# CPU.net
KiCad netlist of a schematic drawn in Altium Designer
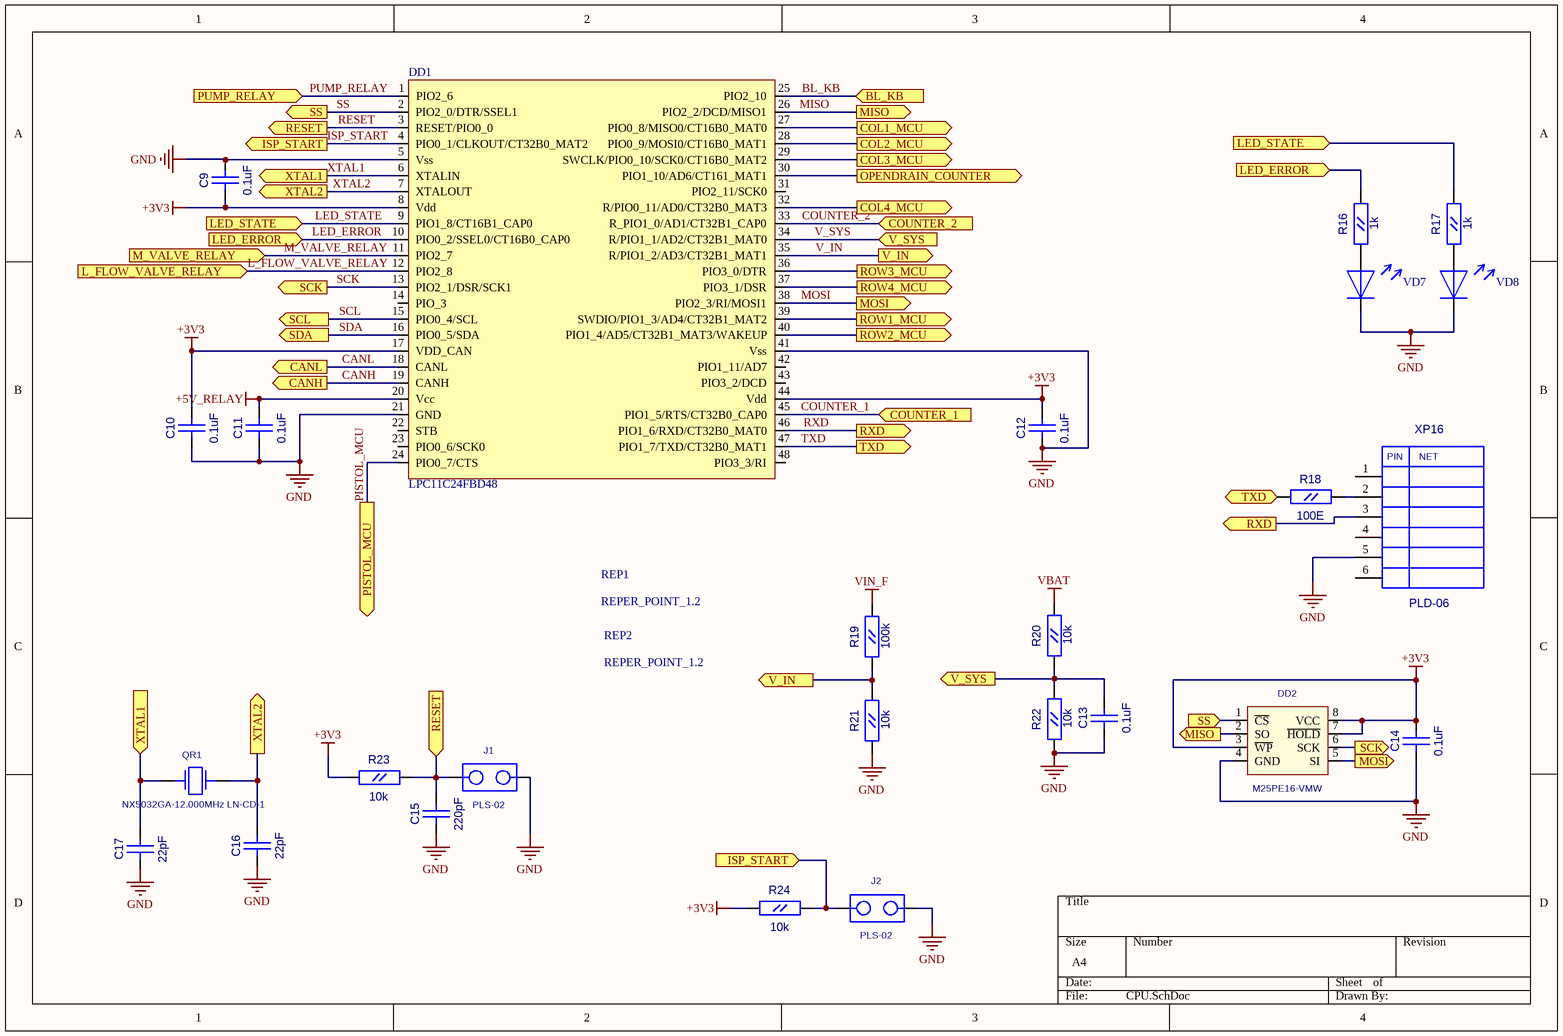
[diagram p0: CPU.SchDoc]

(export (version "E")
  (design (tool "Eeschema 10.0.6"))
  (components
    (comp (ref "C9")
      (value "0.1uF")
      (footprint "CC0603")
      (description "CC0603")
      (libsource (lib "gprs_modem_2") (part "CC0603"))
    )
    (comp (ref "C10")
      (value "0.1uF")
      (footprint "CC0603")
      (description "CC0603")
      (libsource (lib "gprs_modem_2") (part "CC0603"))
    )
    (comp (ref "C11")
      (value "0.1uF")
      (footprint "CC0603")
      (description "CC0603")
      (libsource (lib "gprs_modem_2") (part "CC0603"))
    )
    (comp (ref "C12")
      (value "0.1uF")
      (footprint "CC0603")
      (description "CC0603")
      (libsource (lib "gprs_modem_2") (part "CC0603"))
    )
    (comp (ref "C13")
      (value "0.1uF")
      (footprint "CC0603")
      (description "CC0603")
      (libsource (lib "gprs_modem_2") (part "CC0603"))
    )
    (comp (ref "C14")
      (value "0.1uF")
      (footprint "CC0603")
      (description "CC0603")
      (libsource (lib "gprs_modem_2") (part "CC0603"))
    )
    (comp (ref "C15")
      (value "220pF")
      (footprint "CC0603")
      (description "CC0603")
      (libsource (lib "gprs_modem_2") (part "CC0603"))
    )
    (comp (ref "C16")
      (value "22pF")
      (footprint "CC0603")
      (description "CC0603")
      (libsource (lib "gprs_modem_2") (part "CC0603"))
    )
    (comp (ref "C17")
      (value "22pF")
      (footprint "CC0603")
      (description "CC0603")
      (libsource (lib "gprs_modem_2") (part "CC0603"))
    )
    (comp (ref "DD1")
      (value "LPC11C24FBD48")
      (footprint "LQFP-48")
      (libsource (lib "gprs_modem_2") (part "LPC11C24FBD48"))
    )
    (comp (ref "DD2")
      (value "M25PE16-VMW")
      (footprint "EIAJ_SO8")
      (description "S25FL016A0LMFI01")
      (libsource (lib "gprs_modem_2") (part "S25FL016A0LMFI01"))
    )
    (comp (ref "J1") (value "PLS-02") (footprint "PLS-02") (libsource (lib "gprs_modem_2") (part "PLS-02")))
    (comp (ref "J2") (value "PLS-02") (footprint "PLS-02") (libsource (lib "gprs_modem_2") (part "PLS-02")))
    (comp (ref "QR1")
      (value "NX5032GA-12.000MHz LN-CD-1")
      (footprint "AC5032_2")
      (description "AC5032/2")
      (libsource (lib "gprs_modem_2") (part "AC5032_2"))
    )
    (comp (ref "R16")
      (value "1k")
      (footprint "RC0603")
      (description "RC0603")
      (libsource (lib "gprs_modem_2") (part "RC0603"))
    )
    (comp (ref "R17")
      (value "1k")
      (footprint "RC0603")
      (description "RC0603")
      (libsource (lib "gprs_modem_2") (part "RC0603"))
    )
    (comp (ref "R18")
      (value "100E")
      (footprint "RC0603")
      (description "RC0603")
      (libsource (lib "gprs_modem_2") (part "RC0603"))
    )
    (comp (ref "R19")
      (value "100k")
      (footprint "RC0603")
      (description "RC0603")
      (libsource (lib "gprs_modem_2") (part "RC0603"))
    )
    (comp (ref "R20")
      (value "10k")
      (footprint "RC0603")
      (description "RC0603")
      (libsource (lib "gprs_modem_2") (part "RC0603"))
    )
    (comp (ref "R21")
      (value "10k")
      (footprint "RC0603")
      (description "RC0603")
      (libsource (lib "gprs_modem_2") (part "RC0603"))
    )
    (comp (ref "R22")
      (value "10k")
      (footprint "RC0603")
      (description "RC0603")
      (libsource (lib "gprs_modem_2") (part "RC0603"))
    )
    (comp (ref "R23")
      (value "10k")
      (footprint "RC0603")
      (description "RC0603")
      (libsource (lib "gprs_modem_2") (part "RC0603"))
    )
    (comp (ref "R24")
      (value "10k")
      (footprint "RC0603")
      (description "RC0603")
      (libsource (lib "gprs_modem_2") (part "RC0603"))
    )
    (comp (ref "REP1")
      (value "REPER_POINT_1.2")
      (footprint "REPER1.2")
      (description "REPER1.2")
      (libsource (lib "gprs_modem_2") (part "REPER1.2"))
    )
    (comp (ref "REP2")
      (value "REPER_POINT_1.2")
      (footprint "REPER1.2")
      (description "REPER1.2")
      (libsource (lib "gprs_modem_2") (part "REPER1.2"))
    )
    (comp (ref "VD7")
      (value "LED_0805")
      (footprint "LED0805")
      (libsource (lib "gprs_modem_2") (part "LED_0805"))
    )
    (comp (ref "VD8")
      (value "LED_0805")
      (footprint "LED0805")
      (libsource (lib "gprs_modem_2") (part "LED_0805"))
    )
    (comp (ref "XP16")
      (value "PLD-06")
      (footprint "PIN6")
      (description "PLD06")
      (libsource (lib "gprs_modem_2") (part "PLD-06"))
    )
  )
  (nets
    (net (code "1") (name "+3V3") (class "Default")
      (node (ref "C10") (pin "2") (pinfunction "B_2") (pintype "passive"))
      (node (ref "C12") (pin "2") (pinfunction "B_2") (pintype "passive"))
      (node (ref "C14") (pin "2") (pinfunction "B_2") (pintype "passive"))
      (node (ref "C9") (pin "1") (pinfunction "A_1") (pintype "passive"))
      (node (ref "DD1") (pin "17") (pinfunction "VDD_CAN_17") (pintype "passive"))
      (node (ref "DD1") (pin "44") (pinfunction "Vdd_44") (pintype "passive"))
      (node (ref "DD1") (pin "8") (pinfunction "Vdd_8") (pintype "passive"))
      (node (ref "DD2") (pin "3") (pinfunction "~{WP}_3") (pintype "passive"))
      (node (ref "DD2") (pin "7") (pinfunction "~{HOLD}_7") (pintype "passive"))
      (node (ref "DD2") (pin "8") (pinfunction "VCC_8") (pintype "passive"))
      (node (ref "R23") (pin "1") (pinfunction "A_1") (pintype "passive"))
      (node (ref "R24") (pin "1") (pinfunction "A_1") (pintype "passive"))
    )
    (net (code "2") (name "+5V_RELAY") (class "Default")
      (node (ref "C11") (pin "2") (pinfunction "B_2") (pintype "passive"))
      (node (ref "DD1") (pin "20") (pinfunction "Vcc_20") (pintype "passive"))
    )
    (net (code "3") (name "/BL_KB") (class "Default")
      (node (ref "DD1") (pin "25") (pinfunction "PIO2_10_25") (pintype "passive"))
    )
    (net (code "4") (name "/CANH") (class "Default")
      (node (ref "DD1") (pin "19") (pinfunction "CANH_19") (pintype "passive"))
    )
    (net (code "5") (name "/CANL") (class "Default")
      (node (ref "DD1") (pin "18") (pinfunction "CANL_18") (pintype "passive"))
    )
    (net (code "6") (name "/COL1_MCU") (class "Default")
      (node (ref "DD1") (pin "27") (pinfunction "PIO0_8/MISO0/CT16B0_MAT0_27") (pintype "passive"))
    )
    (net (code "7") (name "/COL2_MCU") (class "Default")
      (node (ref "DD1") (pin "28") (pinfunction "PIO0_9/MOSI0/CT16B0_MAT1_28") (pintype "passive"))
    )
    (net (code "8") (name "/COL3_MCU") (class "Default")
      (node (ref "DD1") (pin "29") (pinfunction "SWCLK/PIO0_10/SCK0/CT16B0_MAT2_29") (pintype "passive"))
    )
    (net (code "9") (name "/COL4_MCU") (class "Default")
      (node (ref "DD1") (pin "32") (pinfunction "R/PIO0_11/AD0/CT32B0_MAT3_32") (pintype "passive"))
    )
    (net (code "10") (name "/COUNTER_1") (class "Default")
      (node (ref "DD1") (pin "45") (pinfunction "PIO1_5/RTS/CT32B0_CAP0_45") (pintype "passive"))
    )
    (net (code "11") (name "/COUNTER_2") (class "Default")
      (node (ref "DD1") (pin "33") (pinfunction "R_PIO1_0/AD1/CT32B1_CAP0_33") (pintype "passive"))
    )
    (net (code "12") (name "/ISP_START") (class "Default")
      (node (ref "DD1") (pin "4") (pinfunction "PIO0_1/CLKOUT/CT32B0_MAT2_4") (pintype "passive"))
      (node (ref "J2") (pin "1") (pintype "passive"))
      (node (ref "R24") (pin "2") (pinfunction "B_2") (pintype "passive"))
    )
    (net (code "13") (name "/LED_ERROR") (class "Default")
      (node (ref "DD1") (pin "10") (pinfunction "PIO0_2/SSEL0/CT16B0_CAP0_10") (pintype "passive"))
      (node (ref "R16") (pin "2") (pinfunction "B_2") (pintype "passive"))
    )
    (net (code "14") (name "/LED_STATE") (class "Default")
      (node (ref "DD1") (pin "9") (pinfunction "PIO1_8/CT16B1_CAP0_9") (pintype "passive"))
      (node (ref "R17") (pin "2") (pinfunction "B_2") (pintype "passive"))
    )
    (net (code "15") (name "/L_FLOW_VALVE_RELAY") (class "Default")
      (node (ref "DD1") (pin "12") (pinfunction "PIO2_8_12") (pintype "passive"))
    )
    (net (code "16") (name "/MISO") (class "Default")
      (node (ref "DD1") (pin "26") (pinfunction "PIO2_2/DCD/MISO1_26") (pintype "passive"))
      (node (ref "DD2") (pin "2") (pinfunction "SO_2") (pintype "passive"))
    )
    (net (code "17") (name "/MOSI") (class "Default")
      (node (ref "DD1") (pin "38") (pinfunction "PIO2_3/RI/MOSI1_38") (pintype "passive"))
      (node (ref "DD2") (pin "5") (pinfunction "SI_5") (pintype "passive"))
    )
    (net (code "18") (name "/M_VALVE_RELAY") (class "Default")
      (node (ref "DD1") (pin "11") (pinfunction "PIO2_7_11") (pintype "passive"))
    )
    (net (code "19") (name "/OPENDRAIN_COUNTER") (class "Default")
      (node (ref "DD1") (pin "30") (pinfunction "PIO1_10/AD6/CT161_MAT1_30") (pintype "passive"))
    )
    (net (code "20") (name "/PISTOL_MCU") (class "Default")
      (node (ref "DD1") (pin "24") (pinfunction "PIO0_7/CTS_24") (pintype "passive"))
    )
    (net (code "21") (name "/PUMP_RELAY") (class "Default")
      (node (ref "DD1") (pin "1") (pinfunction "PIO2_6_1") (pintype "passive"))
    )
    (net (code "22") (name "/RESET") (class "Default")
      (node (ref "C15") (pin "2") (pinfunction "B_2") (pintype "passive"))
      (node (ref "DD1") (pin "3") (pinfunction "RESET/PIO0_0_3") (pintype "passive"))
      (node (ref "J1") (pin "1") (pintype "passive"))
      (node (ref "R23") (pin "2") (pinfunction "B_2") (pintype "passive"))
    )
    (net (code "23") (name "/ROW1_MCU") (class "Default")
      (node (ref "DD1") (pin "39") (pinfunction "SWDIO/PIO1_3/AD4/CT32B1_MAT2_39") (pintype "passive"))
    )
    (net (code "24") (name "/ROW2_MCU") (class "Default")
      (node (ref "DD1") (pin "40") (pinfunction "PIO1_4/AD5/CT32B1_MAT3/WAKEUP_40") (pintype "passive"))
    )
    (net (code "25") (name "/ROW3_MCU") (class "Default")
      (node (ref "DD1") (pin "36") (pinfunction "PIO3_0/DTR_36") (pintype "passive"))
    )
    (net (code "26") (name "/ROW4_MCU") (class "Default")
      (node (ref "DD1") (pin "37") (pinfunction "PIO3_1/DSR_37") (pintype "passive"))
    )
    (net (code "27") (name "/RXD") (class "Default")
      (node (ref "DD1") (pin "46") (pinfunction "PIO1_6/RXD/CT32B0_MAT0_46") (pintype "passive"))
      (node (ref "XP16") (pin "3") (pinfunction "3_3") (pintype "passive"))
    )
    (net (code "28") (name "/SCK") (class "Default")
      (node (ref "DD1") (pin "13") (pinfunction "PIO2_1/DSR/SCK1_13") (pintype "passive"))
      (node (ref "DD2") (pin "6") (pinfunction "SCK_6") (pintype "passive"))
    )
    (net (code "29") (name "/SCL") (class "Default")
      (node (ref "DD1") (pin "15") (pinfunction "PIO0_4/SCL_15") (pintype "passive"))
    )
    (net (code "30") (name "/SDA") (class "Default")
      (node (ref "DD1") (pin "16") (pinfunction "PIO0_5/SDA_16") (pintype "passive"))
    )
    (net (code "31") (name "/SS") (class "Default")
      (node (ref "DD1") (pin "2") (pinfunction "PIO2_0/DTR/SSEL1_2") (pintype "passive"))
      (node (ref "DD2") (pin "1") (pinfunction "~{CS}_1") (pintype "passive"))
    )
    (net (code "32") (name "/TXD") (class "Default")
      (node (ref "DD1") (pin "47") (pinfunction "PIO1_7/TXD/CT32B0_MAT1_47") (pintype "passive"))
      (node (ref "R18") (pin "1") (pinfunction "A_1") (pintype "passive"))
    )
    (net (code "33") (name "/V_IN") (class "Default")
      (node (ref "DD1") (pin "35") (pinfunction "R/PIO1_2/AD3/CT32B1_MAT1_35") (pintype "passive"))
      (node (ref "R19") (pin "1") (pinfunction "A_1") (pintype "passive"))
      (node (ref "R21") (pin "2") (pinfunction "B_2") (pintype "passive"))
    )
    (net (code "34") (name "/V_SYS") (class "Default")
      (node (ref "C13") (pin "2") (pinfunction "B_2") (pintype "passive"))
      (node (ref "DD1") (pin "34") (pinfunction "R/PIO1_1/AD2/CT32B1_MAT0_34") (pintype "passive"))
      (node (ref "R20") (pin "1") (pinfunction "A_1") (pintype "passive"))
      (node (ref "R22") (pin "2") (pinfunction "B_2") (pintype "passive"))
    )
    (net (code "35") (name "/XTAL1") (class "Default")
      (node (ref "C17") (pin "2") (pinfunction "B_2") (pintype "passive"))
      (node (ref "DD1") (pin "6") (pinfunction "XTALIN_6") (pintype "passive"))
      (node (ref "QR1") (pin "1") (pintype "passive"))
    )
    (net (code "36") (name "/XTAL2") (class "Default")
      (node (ref "C16") (pin "2") (pinfunction "B_2") (pintype "passive"))
      (node (ref "DD1") (pin "7") (pinfunction "XTALOUT_7") (pintype "passive"))
      (node (ref "QR1") (pin "2") (pintype "passive"))
    )
    (net (code "37") (name "GND") (class "Default")
      (node (ref "C10") (pin "1") (pinfunction "A_1") (pintype "passive"))
      (node (ref "C11") (pin "1") (pinfunction "A_1") (pintype "passive"))
      (node (ref "C12") (pin "1") (pinfunction "A_1") (pintype "passive"))
      (node (ref "C13") (pin "1") (pinfunction "A_1") (pintype "passive"))
      (node (ref "C14") (pin "1") (pinfunction "A_1") (pintype "passive"))
      (node (ref "C15") (pin "1") (pinfunction "A_1") (pintype "passive"))
      (node (ref "C16") (pin "1") (pinfunction "A_1") (pintype "passive"))
      (node (ref "C17") (pin "1") (pinfunction "A_1") (pintype "passive"))
      (node (ref "C9") (pin "2") (pinfunction "B_2") (pintype "passive"))
      (node (ref "DD1") (pin "21") (pinfunction "GND_21") (pintype "passive"))
      (node (ref "DD1") (pin "41") (pinfunction "Vss_41") (pintype "passive"))
      (node (ref "DD1") (pin "5") (pinfunction "Vss_5") (pintype "passive"))
      (node (ref "DD2") (pin "4") (pinfunction "GND_4") (pintype "passive"))
      (node (ref "J1") (pin "2") (pintype "passive"))
      (node (ref "J2") (pin "2") (pintype "passive"))
      (node (ref "R21") (pin "1") (pinfunction "A_1") (pintype "passive"))
      (node (ref "R22") (pin "1") (pinfunction "A_1") (pintype "passive"))
      (node (ref "VD7") (pin "2") (pintype "passive"))
      (node (ref "VD8") (pin "2") (pintype "passive"))
      (node (ref "XP16") (pin "5") (pinfunction "5_5") (pintype "passive"))
    )
    (net (code "38") (name "Net-(R16-A)") (class "Default")
      (node (ref "R16") (pin "1") (pinfunction "A_1") (pintype "passive"))
      (node (ref "VD7") (pin "1") (pintype "passive"))
    )
    (net (code "39") (name "Net-(R17-A)") (class "Default")
      (node (ref "R17") (pin "1") (pinfunction "A_1") (pintype "passive"))
      (node (ref "VD8") (pin "1") (pintype "passive"))
    )
    (net (code "40") (name "Net-(R18-B)") (class "Default")
      (node (ref "R18") (pin "2") (pinfunction "B_2") (pintype "passive"))
      (node (ref "XP16") (pin "2") (pinfunction "2_2") (pintype "passive"))
    )
    (net (code "41") (name "VBAT") (class "Default")
      (node (ref "R20") (pin "2") (pinfunction "B_2") (pintype "passive"))
    )
    (net (code "42") (name "VIN_F") (class "Default")
      (node (ref "R19") (pin "2") (pinfunction "B_2") (pintype "passive"))
    )
    (net (code "43") (name "unconnected-(DD1-PIO0_6{slash}SCK0-Pad23)") (class "Default")
      (node (ref "DD1") (pin "23") (pinfunction "PIO0_6/SCK0_23") (pintype "passive"))
    )
    (net (code "44") (name "unconnected-(DD1-PIO1_11{slash}AD7-Pad42)") (class "Default")
      (node (ref "DD1") (pin "42") (pinfunction "PIO1_11/AD7_42") (pintype "passive"))
    )
    (net (code "45") (name "unconnected-(DD1-PIO2_11{slash}SCK0-Pad31)") (class "Default")
      (node (ref "DD1") (pin "31") (pinfunction "PIO2_11/SCK0_31") (pintype "passive"))
    )
    (net (code "46") (name "unconnected-(DD1-PIO3_2{slash}DCD-Pad43)") (class "Default")
      (node (ref "DD1") (pin "43") (pinfunction "PIO3_2/DCD_43") (pintype "passive"))
    )
    (net (code "47") (name "unconnected-(DD1-PIO3_3{slash}RI-Pad48)") (class "Default")
      (node (ref "DD1") (pin "48") (pinfunction "PIO3_3/RI_48") (pintype "passive"))
    )
    (net (code "48") (name "unconnected-(DD1-PIO_3-Pad14)") (class "Default")
      (node (ref "DD1") (pin "14") (pinfunction "PIO_3_14") (pintype "passive"))
    )
    (net (code "49") (name "unconnected-(DD1-STB-Pad22)") (class "Default")
      (node (ref "DD1") (pin "22") (pinfunction "STB_22") (pintype "passive"))
    )
    (net (code "50") (name "unconnected-(REP1-Pad1)") (class "Default")
      (node (ref "REP1") (pin "1") (pintype "passive"))
    )
    (net (code "51") (name "unconnected-(REP2-Pad1)") (class "Default")
      (node (ref "REP2") (pin "1") (pintype "passive"))
    )
    (net (code "52") (name "unconnected-(XP16-Pad1)") (class "Default")
      (node (ref "XP16") (pin "1") (pinfunction "1_1") (pintype "passive"))
    )
    (net (code "53") (name "unconnected-(XP16-Pad4)") (class "Default")
      (node (ref "XP16") (pin "4") (pinfunction "4_4") (pintype "passive"))
    )
    (net (code "54") (name "unconnected-(XP16-Pad6)") (class "Default")
      (node (ref "XP16") (pin "6") (pinfunction "6_6") (pintype "passive"))
    )
  )
)
